# SCH_BZ_bizcard_source.net
KiCad netlist of a schematic drawn in EasyEDA
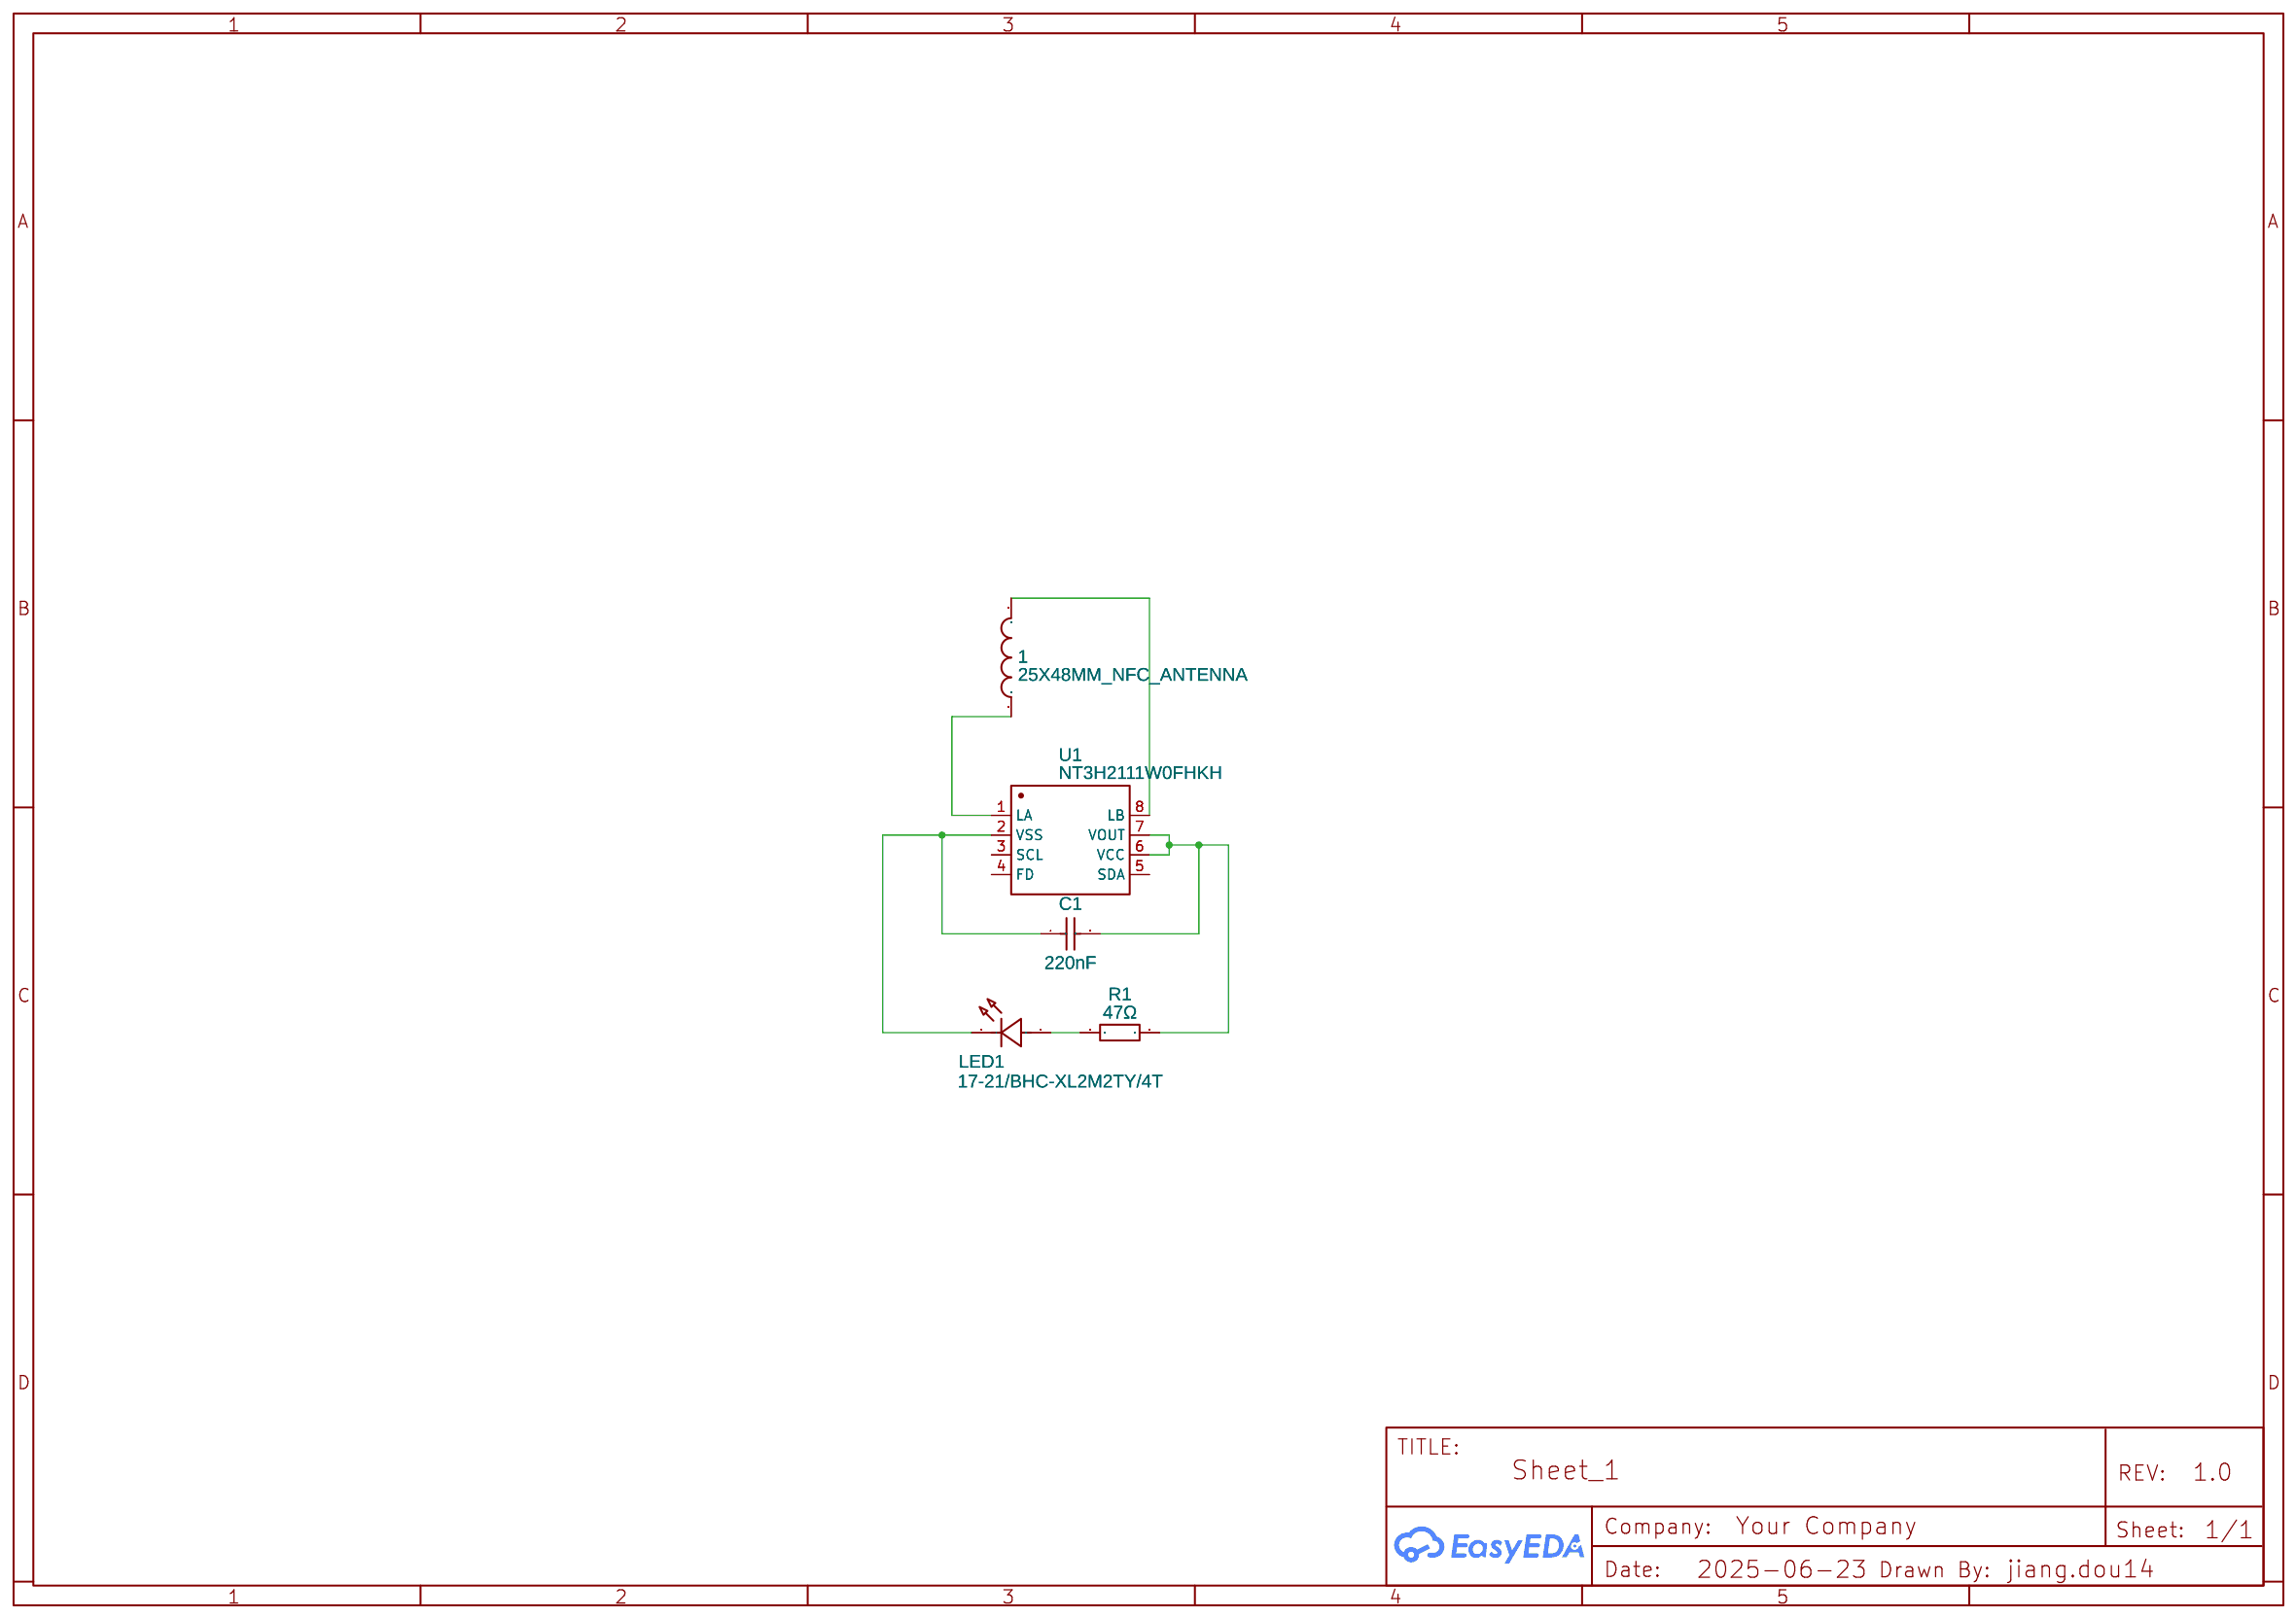
[diagram p0: schematic sheet]

(export (version "E")
  (design (tool "Eeschema 10.0.6"))
  (components
    (comp (ref "1") (value "25X48MM_NFC_ANTENNA") (libsource (lib "") (part "25X48MM_NFC_ANTENNA")))
    (comp (ref "C1")
      (value "220nF")
      (fields
        (field (name "Manufacturer Part") "CL10B224KA8NNNC")
        (field (name "Manufacturer") "SAMSUNG(三星)")
      )
      (libsource (lib "") (part "CL10B224KA8NNNC"))
    )
    (comp (ref "LED1")
      (value "17-21/BHC-XL2M2TY/4T")
      (fields (field (name "Manufacturer") "EVERLIGHT(亿光)"))
      (libsource (lib "") (part "17-21/BHC-XL2M2TY/4T"))
    )
    (comp (ref "R1")
      (value "47Ω")
      (fields
        (field (name "Manufacturer Part") "0603WAF470JT5E")
        (field (name "Manufacturer") "UNI-ROYAL(厚声)")
      )
      (libsource (lib "") (part "0603WAF470JT5E"))
    )
    (comp (ref "U1")
      (value "NT3H2111W0FHKH")
      (fields (field (name "Manufacturer") "NXP(恩智浦)"))
      (libsource (lib "") (part "NT3H2111W0FHKH"))
    )
  )
  (nets
    (net (code "1") (name "Net-(LED1-+)") (class "Default")
      (node (ref "LED1") (pin "1") (pinfunction "+_1") (pintype "unspecified"))
      (node (ref "R1") (pin "2") (pinfunction "2_2") (pintype "input"))
    )
    (net (code "2") (name "Net-(LED1--)") (class "Default")
      (node (ref "C1") (pin "1") (pinfunction "1_1") (pintype "input"))
      (node (ref "LED1") (pin "2") (pinfunction "-_2") (pintype "unspecified"))
      (node (ref "U1") (pin "2") (pinfunction "VSS_2") (pintype "unspecified"))
    )
    (net (code "3") (name "Net-(U1-LA)") (class "Default")
      (node (ref "1") (pin "P$1") (pinfunction "P$1_P$1") (pintype "bidirectional"))
      (node (ref "U1") (pin "1") (pinfunction "LA_1") (pintype "unspecified"))
    )
    (net (code "4") (name "Net-(U1-LB)") (class "Default")
      (node (ref "1") (pin "P$2") (pinfunction "P$2_P$2") (pintype "bidirectional"))
      (node (ref "U1") (pin "8") (pinfunction "LB_8") (pintype "unspecified"))
    )
    (net (code "5") (name "Net-(U1-VCC)") (class "Default")
      (node (ref "C1") (pin "2") (pinfunction "2_2") (pintype "input"))
      (node (ref "R1") (pin "1") (pinfunction "1_1") (pintype "input"))
      (node (ref "U1") (pin "6") (pinfunction "VCC_6") (pintype "unspecified"))
      (node (ref "U1") (pin "7") (pinfunction "VOUT_7") (pintype "unspecified"))
    )
    (net (code "6") (name "unconnected-(U1-FD-Pad4)") (class "Default")
      (node (ref "U1") (pin "4") (pinfunction "FD_4") (pintype "unspecified"))
    )
    (net (code "7") (name "unconnected-(U1-SCL-Pad3)") (class "Default")
      (node (ref "U1") (pin "3") (pinfunction "SCL_3") (pintype "unspecified"))
    )
    (net (code "8") (name "unconnected-(U1-SDA-Pad5)") (class "Default")
      (node (ref "U1") (pin "5") (pinfunction "SDA_5") (pintype "unspecified"))
    )
  )
)
